# example-ao-circuits.net
KiCad netlist of a schematic drawn in EAGLE
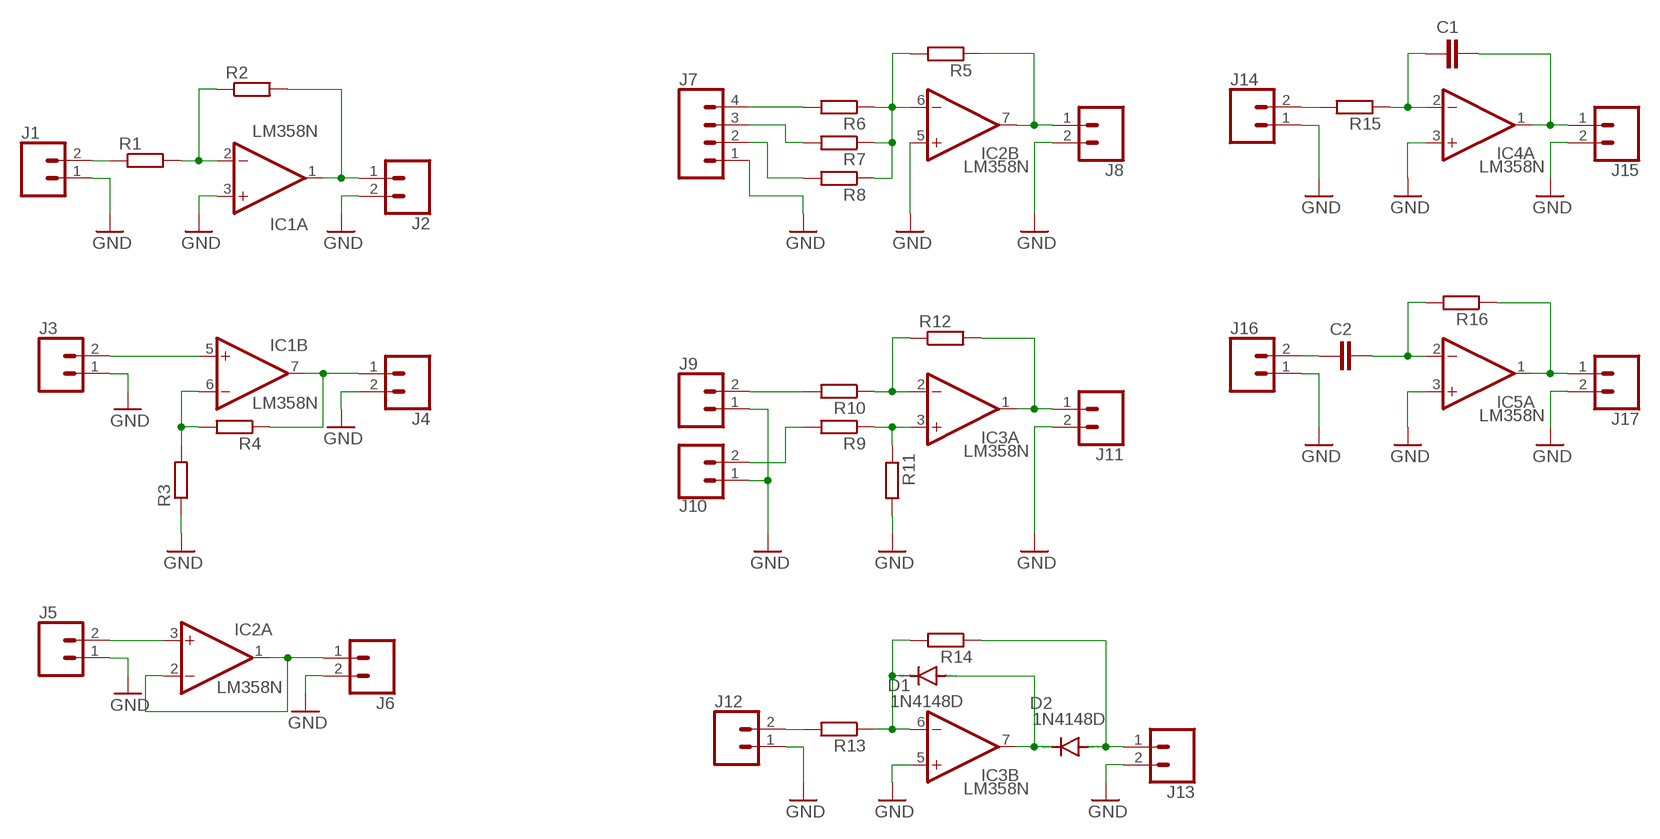
[diagram p0: schematic, sheet 1]

(export (version "E")
  (design (tool "Eeschema 10.0.6"))
  (components
    (comp (ref "C1")
      (value "C-EU025-030X050")
      (footprint "eagle-import:C025-030X050")
      (libsource (lib "eagle-import") (part "C-EU025-030X050"))
    )
    (comp (ref "C2")
      (value "C-EU025-030X050")
      (footprint "eagle-import:C025-030X050")
      (libsource (lib "eagle-import") (part "C-EU025-030X050"))
    )
    (comp (ref "D1")
      (value "1N4148D")
      (footprint "eagle-import:DO35-10")
      (libsource (lib "eagle-import") (part "1N4148DO35-10"))
    )
    (comp (ref "D2")
      (value "1N4148D")
      (footprint "eagle-import:DO35-10")
      (libsource (lib "eagle-import") (part "1N4148DO35-10"))
    )
    (comp (ref "IC1")
      (value "LM358N")
      (footprint "eagle-import:DIL08")
      (libsource (lib "eagle-import") (part "LM358N"))
    )
    (comp (ref "IC2")
      (value "LM358N")
      (footprint "eagle-import:DIL08")
      (libsource (lib "eagle-import") (part "LM358N"))
    )
    (comp (ref "IC3")
      (value "LM358N")
      (footprint "eagle-import:DIL08")
      (libsource (lib "eagle-import") (part "LM358N"))
    )
    (comp (ref "IC4")
      (value "LM358N")
      (footprint "eagle-import:DIL08")
      (libsource (lib "eagle-import") (part "LM358N"))
    )
    (comp (ref "IC5")
      (value "LM358N")
      (footprint "eagle-import:DIL08")
      (libsource (lib "eagle-import") (part "LM358N"))
    )
    (comp (ref "J1")
      (value "CONN_02")
      (footprint "eagle-import:1X02")
      (libsource (lib "eagle-import") (part "CONN_02"))
    )
    (comp (ref "J2")
      (value "CONN_02")
      (footprint "eagle-import:1X02")
      (libsource (lib "eagle-import") (part "CONN_02"))
    )
    (comp (ref "J3")
      (value "CONN_02")
      (footprint "eagle-import:1X02")
      (libsource (lib "eagle-import") (part "CONN_02"))
    )
    (comp (ref "J4")
      (value "CONN_02")
      (footprint "eagle-import:1X02")
      (libsource (lib "eagle-import") (part "CONN_02"))
    )
    (comp (ref "J5")
      (value "CONN_02")
      (footprint "eagle-import:1X02")
      (libsource (lib "eagle-import") (part "CONN_02"))
    )
    (comp (ref "J6")
      (value "CONN_02")
      (footprint "eagle-import:1X02")
      (libsource (lib "eagle-import") (part "CONN_02"))
    )
    (comp (ref "J7")
      (value "CONN_04PTH")
      (footprint "eagle-import:1X04")
      (libsource (lib "eagle-import") (part "CONN_04PTH"))
    )
    (comp (ref "J8")
      (value "CONN_02")
      (footprint "eagle-import:1X02")
      (libsource (lib "eagle-import") (part "CONN_02"))
    )
    (comp (ref "J9")
      (value "CONN_02")
      (footprint "eagle-import:1X02")
      (libsource (lib "eagle-import") (part "CONN_02"))
    )
    (comp (ref "J10")
      (value "CONN_02")
      (footprint "eagle-import:1X02")
      (libsource (lib "eagle-import") (part "CONN_02"))
    )
    (comp (ref "J11")
      (value "CONN_02")
      (footprint "eagle-import:1X02")
      (libsource (lib "eagle-import") (part "CONN_02"))
    )
    (comp (ref "J12")
      (value "CONN_02")
      (footprint "eagle-import:1X02")
      (libsource (lib "eagle-import") (part "CONN_02"))
    )
    (comp (ref "J13")
      (value "CONN_02")
      (footprint "eagle-import:1X02")
      (libsource (lib "eagle-import") (part "CONN_02"))
    )
    (comp (ref "J14")
      (value "CONN_02")
      (footprint "eagle-import:1X02")
      (libsource (lib "eagle-import") (part "CONN_02"))
    )
    (comp (ref "J15")
      (value "CONN_02")
      (footprint "eagle-import:1X02")
      (libsource (lib "eagle-import") (part "CONN_02"))
    )
    (comp (ref "J16")
      (value "CONN_02")
      (footprint "eagle-import:1X02")
      (libsource (lib "eagle-import") (part "CONN_02"))
    )
    (comp (ref "J17")
      (value "CONN_02")
      (footprint "eagle-import:1X02")
      (libsource (lib "eagle-import") (part "CONN_02"))
    )
    (comp (ref "R1")
      (value "R-EU_0207/10")
      (footprint "eagle-import:0207_10")
      (libsource (lib "eagle-import") (part "R-EU_0207/10"))
    )
    (comp (ref "R2")
      (value "R-EU_0207/10")
      (footprint "eagle-import:0207_10")
      (libsource (lib "eagle-import") (part "R-EU_0207/10"))
    )
    (comp (ref "R3")
      (value "R-EU_0207/10")
      (footprint "eagle-import:0207_10")
      (libsource (lib "eagle-import") (part "R-EU_0207/10"))
    )
    (comp (ref "R4")
      (value "R-EU_0207/10")
      (footprint "eagle-import:0207_10")
      (libsource (lib "eagle-import") (part "R-EU_0207/10"))
    )
    (comp (ref "R5")
      (value "R-EU_0207/10")
      (footprint "eagle-import:0207_10")
      (libsource (lib "eagle-import") (part "R-EU_0207/10"))
    )
    (comp (ref "R6")
      (value "R-EU_0207/10")
      (footprint "eagle-import:0207_10")
      (libsource (lib "eagle-import") (part "R-EU_0207/10"))
    )
    (comp (ref "R7")
      (value "R-EU_0207/10")
      (footprint "eagle-import:0207_10")
      (libsource (lib "eagle-import") (part "R-EU_0207/10"))
    )
    (comp (ref "R8")
      (value "R-EU_0207/10")
      (footprint "eagle-import:0207_10")
      (libsource (lib "eagle-import") (part "R-EU_0207/10"))
    )
    (comp (ref "R9")
      (value "R-EU_0207/10")
      (footprint "eagle-import:0207_10")
      (libsource (lib "eagle-import") (part "R-EU_0207/10"))
    )
    (comp (ref "R10")
      (value "R-EU_0207/10")
      (footprint "eagle-import:0207_10")
      (libsource (lib "eagle-import") (part "R-EU_0207/10"))
    )
    (comp (ref "R11")
      (value "R-EU_0207/10")
      (footprint "eagle-import:0207_10")
      (libsource (lib "eagle-import") (part "R-EU_0207/10"))
    )
    (comp (ref "R12")
      (value "R-EU_0207/10")
      (footprint "eagle-import:0207_10")
      (libsource (lib "eagle-import") (part "R-EU_0207/10"))
    )
    (comp (ref "R13")
      (value "R-EU_0207/10")
      (footprint "eagle-import:0207_10")
      (libsource (lib "eagle-import") (part "R-EU_0207/10"))
    )
    (comp (ref "R14")
      (value "R-EU_0207/10")
      (footprint "eagle-import:0207_10")
      (libsource (lib "eagle-import") (part "R-EU_0207/10"))
    )
    (comp (ref "R15")
      (value "R-EU_0207/10")
      (footprint "eagle-import:0207_10")
      (libsource (lib "eagle-import") (part "R-EU_0207/10"))
    )
    (comp (ref "R16")
      (value "R-EU_0207/10")
      (footprint "eagle-import:0207_10")
      (libsource (lib "eagle-import") (part "R-EU_0207/10"))
    )
  )
  (nets
    (net (code "1") (name "GND") (class "Default")
      (node (ref "IC1") (pin "3") (pinfunction "+IN_3") (pintype "input"))
      (node (ref "IC2") (pin "5") (pinfunction "+IN_5") (pintype "input"))
      (node (ref "IC3") (pin "5") (pinfunction "+IN_5") (pintype "input"))
      (node (ref "IC4") (pin "3") (pinfunction "+IN_3") (pintype "input"))
      (node (ref "IC5") (pin "3") (pinfunction "+IN_3") (pintype "input"))
      (node (ref "J1") (pin "1") (pinfunction "1_1") (pintype "passive"))
      (node (ref "J10") (pin "1") (pinfunction "1_1") (pintype "passive"))
      (node (ref "J11") (pin "2") (pinfunction "2_2") (pintype "passive"))
      (node (ref "J12") (pin "1") (pinfunction "1_1") (pintype "passive"))
      (node (ref "J13") (pin "2") (pinfunction "2_2") (pintype "passive"))
      (node (ref "J14") (pin "1") (pinfunction "1_1") (pintype "passive"))
      (node (ref "J15") (pin "2") (pinfunction "2_2") (pintype "passive"))
      (node (ref "J16") (pin "1") (pinfunction "1_1") (pintype "passive"))
      (node (ref "J17") (pin "2") (pinfunction "2_2") (pintype "passive"))
      (node (ref "J2") (pin "2") (pinfunction "2_2") (pintype "passive"))
      (node (ref "J3") (pin "1") (pinfunction "1_1") (pintype "passive"))
      (node (ref "J4") (pin "2") (pinfunction "2_2") (pintype "passive"))
      (node (ref "J5") (pin "1") (pinfunction "1_1") (pintype "passive"))
      (node (ref "J6") (pin "2") (pinfunction "2_2") (pintype "passive"))
      (node (ref "J7") (pin "1") (pinfunction "1_1") (pintype "passive"))
      (node (ref "J8") (pin "2") (pinfunction "2_2") (pintype "passive"))
      (node (ref "J9") (pin "1") (pinfunction "1_1") (pintype "passive"))
      (node (ref "R11") (pin "2") (pinfunction "2_2") (pintype "passive"))
      (node (ref "R3") (pin "1") (pinfunction "1_1") (pintype "passive"))
    )
    (net (code "2") (name "Net-(C2-Pad1)") (class "Default")
      (node (ref "C2") (pin "1") (pinfunction "1_1") (pintype "passive"))
      (node (ref "J16") (pin "2") (pinfunction "2_2") (pintype "passive"))
    )
    (net (code "3") (name "Net-(D2-PadA)") (class "Default")
      (node (ref "D2") (pin "A") (pinfunction "A_A") (pintype "passive"))
      (node (ref "J13") (pin "1") (pinfunction "1_1") (pintype "passive"))
      (node (ref "R14") (pin "1") (pinfunction "1_1") (pintype "passive"))
    )
    (net (code "4") (name "Net-(IC1A--IN)") (class "Default")
      (node (ref "IC1") (pin "2") (pinfunction "-IN_2") (pintype "input"))
      (node (ref "R1") (pin "2") (pinfunction "2_2") (pintype "passive"))
      (node (ref "R2") (pin "1") (pinfunction "1_1") (pintype "passive"))
    )
    (net (code "5") (name "Net-(IC1A-OUT)") (class "Default")
      (node (ref "IC1") (pin "1") (pinfunction "OUT_1") (pintype "output"))
      (node (ref "J2") (pin "1") (pinfunction "1_1") (pintype "passive"))
      (node (ref "R2") (pin "2") (pinfunction "2_2") (pintype "passive"))
    )
    (net (code "6") (name "Net-(IC1B-+IN)") (class "Default")
      (node (ref "IC1") (pin "5") (pinfunction "+IN_5") (pintype "input"))
      (node (ref "J3") (pin "2") (pinfunction "2_2") (pintype "passive"))
    )
    (net (code "7") (name "Net-(IC1B--IN)") (class "Default")
      (node (ref "IC1") (pin "6") (pinfunction "-IN_6") (pintype "input"))
      (node (ref "R3") (pin "2") (pinfunction "2_2") (pintype "passive"))
      (node (ref "R4") (pin "2") (pinfunction "2_2") (pintype "passive"))
    )
    (net (code "8") (name "Net-(IC1B-OUT)") (class "Default")
      (node (ref "IC1") (pin "7") (pinfunction "OUT_7") (pintype "output"))
      (node (ref "J4") (pin "1") (pinfunction "1_1") (pintype "passive"))
      (node (ref "R4") (pin "1") (pinfunction "1_1") (pintype "passive"))
    )
    (net (code "9") (name "Net-(IC2A-+IN)") (class "Default")
      (node (ref "IC2") (pin "3") (pinfunction "+IN_3") (pintype "input"))
      (node (ref "J5") (pin "2") (pinfunction "2_2") (pintype "passive"))
    )
    (net (code "10") (name "Net-(IC2A--IN)") (class "Default")
      (node (ref "IC2") (pin "1") (pinfunction "OUT_1") (pintype "output"))
      (node (ref "IC2") (pin "2") (pinfunction "-IN_2") (pintype "input"))
      (node (ref "J6") (pin "1") (pinfunction "1_1") (pintype "passive"))
    )
    (net (code "11") (name "Net-(IC2B--IN)") (class "Default")
      (node (ref "IC2") (pin "6") (pinfunction "-IN_6") (pintype "input"))
      (node (ref "R5") (pin "2") (pinfunction "2_2") (pintype "passive"))
      (node (ref "R6") (pin "1") (pinfunction "1_1") (pintype "passive"))
      (node (ref "R7") (pin "1") (pinfunction "1_1") (pintype "passive"))
      (node (ref "R8") (pin "1") (pinfunction "1_1") (pintype "passive"))
    )
    (net (code "12") (name "Net-(IC2B-OUT)") (class "Default")
      (node (ref "IC2") (pin "7") (pinfunction "OUT_7") (pintype "output"))
      (node (ref "J8") (pin "1") (pinfunction "1_1") (pintype "passive"))
      (node (ref "R5") (pin "1") (pinfunction "1_1") (pintype "passive"))
    )
    (net (code "13") (name "Net-(IC3A-+IN)") (class "Default")
      (node (ref "IC3") (pin "3") (pinfunction "+IN_3") (pintype "input"))
      (node (ref "R11") (pin "1") (pinfunction "1_1") (pintype "passive"))
      (node (ref "R9") (pin "1") (pinfunction "1_1") (pintype "passive"))
    )
    (net (code "14") (name "Net-(IC3A--IN)") (class "Default")
      (node (ref "IC3") (pin "2") (pinfunction "-IN_2") (pintype "input"))
      (node (ref "R10") (pin "1") (pinfunction "1_1") (pintype "passive"))
      (node (ref "R12") (pin "1") (pinfunction "1_1") (pintype "passive"))
    )
    (net (code "15") (name "Net-(IC3A-OUT)") (class "Default")
      (node (ref "IC3") (pin "1") (pinfunction "OUT_1") (pintype "output"))
      (node (ref "J11") (pin "1") (pinfunction "1_1") (pintype "passive"))
      (node (ref "R12") (pin "2") (pinfunction "2_2") (pintype "passive"))
    )
    (net (code "16") (name "Net-(IC3B--IN)") (class "Default")
      (node (ref "D1") (pin "C") (pinfunction "C_C") (pintype "passive"))
      (node (ref "IC3") (pin "6") (pinfunction "-IN_6") (pintype "input"))
      (node (ref "R13") (pin "1") (pinfunction "1_1") (pintype "passive"))
      (node (ref "R14") (pin "2") (pinfunction "2_2") (pintype "passive"))
    )
    (net (code "17") (name "Net-(IC3B-OUT)") (class "Default")
      (node (ref "D1") (pin "A") (pinfunction "A_A") (pintype "passive"))
      (node (ref "D2") (pin "C") (pinfunction "C_C") (pintype "passive"))
      (node (ref "IC3") (pin "7") (pinfunction "OUT_7") (pintype "output"))
    )
    (net (code "18") (name "Net-(IC4A--IN)") (class "Default")
      (node (ref "C1") (pin "1") (pinfunction "1_1") (pintype "passive"))
      (node (ref "IC4") (pin "2") (pinfunction "-IN_2") (pintype "input"))
      (node (ref "R15") (pin "1") (pinfunction "1_1") (pintype "passive"))
    )
    (net (code "19") (name "Net-(IC4A-OUT)") (class "Default")
      (node (ref "C1") (pin "2") (pinfunction "2_2") (pintype "passive"))
      (node (ref "IC4") (pin "1") (pinfunction "OUT_1") (pintype "output"))
      (node (ref "J15") (pin "1") (pinfunction "1_1") (pintype "passive"))
    )
    (net (code "20") (name "Net-(IC5A--IN)") (class "Default")
      (node (ref "C2") (pin "2") (pinfunction "2_2") (pintype "passive"))
      (node (ref "IC5") (pin "2") (pinfunction "-IN_2") (pintype "input"))
      (node (ref "R16") (pin "2") (pinfunction "2_2") (pintype "passive"))
    )
    (net (code "21") (name "Net-(IC5A-OUT)") (class "Default")
      (node (ref "IC5") (pin "1") (pinfunction "OUT_1") (pintype "output"))
      (node (ref "J17") (pin "1") (pinfunction "1_1") (pintype "passive"))
      (node (ref "R16") (pin "1") (pinfunction "1_1") (pintype "passive"))
    )
    (net (code "22") (name "Net-(J1-Pad2)") (class "Default")
      (node (ref "J1") (pin "2") (pinfunction "2_2") (pintype "passive"))
      (node (ref "R1") (pin "1") (pinfunction "1_1") (pintype "passive"))
    )
    (net (code "23") (name "Net-(J7-Pad2)") (class "Default")
      (node (ref "J7") (pin "2") (pinfunction "2_2") (pintype "passive"))
      (node (ref "R8") (pin "2") (pinfunction "2_2") (pintype "passive"))
    )
    (net (code "24") (name "Net-(J7-Pad3)") (class "Default")
      (node (ref "J7") (pin "3") (pinfunction "3_3") (pintype "passive"))
      (node (ref "R7") (pin "2") (pinfunction "2_2") (pintype "passive"))
    )
    (net (code "25") (name "Net-(J7-Pad4)") (class "Default")
      (node (ref "J7") (pin "4") (pinfunction "4_4") (pintype "passive"))
      (node (ref "R6") (pin "2") (pinfunction "2_2") (pintype "passive"))
    )
    (net (code "26") (name "Net-(J9-Pad2)") (class "Default")
      (node (ref "J9") (pin "2") (pinfunction "2_2") (pintype "passive"))
      (node (ref "R10") (pin "2") (pinfunction "2_2") (pintype "passive"))
    )
    (net (code "27") (name "Net-(J10-Pad2)") (class "Default")
      (node (ref "J10") (pin "2") (pinfunction "2_2") (pintype "passive"))
      (node (ref "R9") (pin "2") (pinfunction "2_2") (pintype "passive"))
    )
    (net (code "28") (name "Net-(J12-Pad2)") (class "Default")
      (node (ref "J12") (pin "2") (pinfunction "2_2") (pintype "passive"))
      (node (ref "R13") (pin "2") (pinfunction "2_2") (pintype "passive"))
    )
    (net (code "29") (name "Net-(J14-Pad2)") (class "Default")
      (node (ref "J14") (pin "2") (pinfunction "2_2") (pintype "passive"))
      (node (ref "R15") (pin "2") (pinfunction "2_2") (pintype "passive"))
    )
  )
)
